# PatGenV2.net
KiCad netlist of a schematic drawn in EAGLE
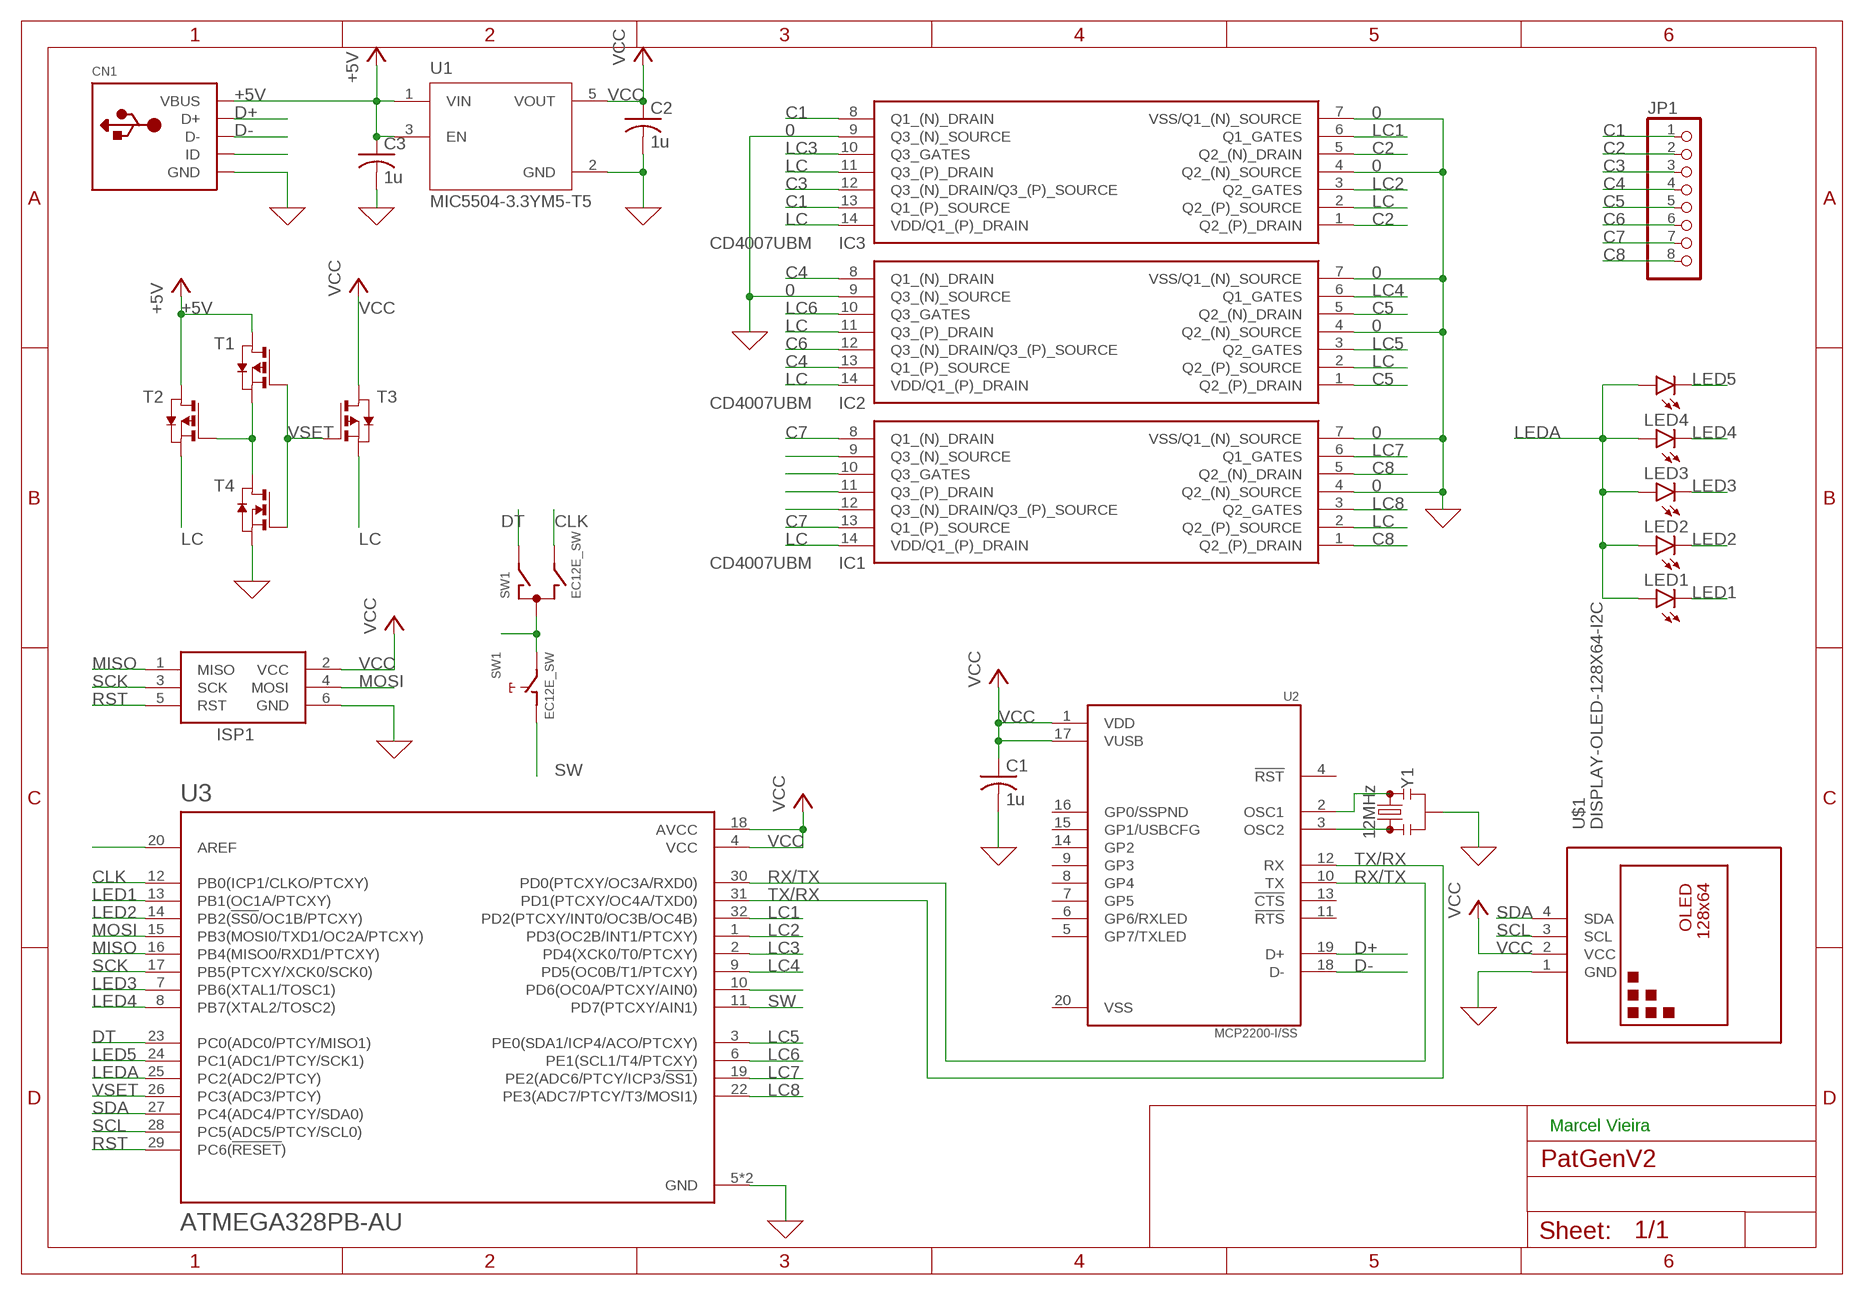
[diagram p0: schematic, sheet 1]

(export (version "E")
  (design (tool "Eeschema 10.0.6"))
  (components
    (comp (ref "C1")
      (value "1u")
      (footprint "eagle-import:C0805")
      (libsource (lib "eagle-import") (part "C-USC0805"))
    )
    (comp (ref "C2")
      (value "1u")
      (footprint "eagle-import:C0805")
      (libsource (lib "eagle-import") (part "C-USC0805"))
    )
    (comp (ref "C3")
      (value "1u")
      (footprint "eagle-import:C0805")
      (libsource (lib "eagle-import") (part "C-USC0805"))
    )
    (comp (ref "CN1")
      (value "USBMINIB")
      (footprint "eagle-import:USB-MINIB")
      (libsource (lib "eagle-import") (part "USBMINIB"))
    )
    (comp (ref "IC1")
      (value "CD4007UBM")
      (footprint "eagle-import:SOIC127P600X175-14N")
      (fields (field (name "MOUSER_PART_NUMBER") "595-CD4007UBM"))
      (libsource (lib "eagle-import") (part "CD4007UBM"))
    )
    (comp (ref "IC2")
      (value "CD4007UBM")
      (footprint "eagle-import:SOIC127P600X175-14N")
      (fields (field (name "MOUSER_PART_NUMBER") "595-CD4007UBM"))
      (libsource (lib "eagle-import") (part "CD4007UBM"))
    )
    (comp (ref "IC3")
      (value "CD4007UBM")
      (footprint "eagle-import:SOIC127P600X175-14N")
      (fields (field (name "MOUSER_PART_NUMBER") "595-CD4007UBM"))
      (libsource (lib "eagle-import") (part "CD4007UBM"))
    )
    (comp (ref "ISP1")
      (value "AVRISP-6")
      (footprint "eagle-import:AVRISP")
      (libsource (lib "eagle-import") (part "AVRISP-6"))
    )
    (comp (ref "JP1")
      (value "PINHD-1X8-3.5MM")
      (footprint "eagle-import:1X08-3.5MM")
      (libsource (lib "eagle-import") (part "PINHD-1X8-3.5MM"))
    )
    (comp (ref "LED1")
      (value "LEDCHIP-LED0805")
      (footprint "eagle-import:CHIP-LED0805")
      (libsource (lib "eagle-import") (part "LEDCHIP-LED0805"))
    )
    (comp (ref "LED2")
      (value "LEDCHIP-LED0805")
      (footprint "eagle-import:CHIP-LED0805")
      (libsource (lib "eagle-import") (part "LEDCHIP-LED0805"))
    )
    (comp (ref "LED3")
      (value "LEDCHIP-LED0805")
      (footprint "eagle-import:CHIP-LED0805")
      (libsource (lib "eagle-import") (part "LEDCHIP-LED0805"))
    )
    (comp (ref "LED4")
      (value "LEDCHIP-LED0805")
      (footprint "eagle-import:CHIP-LED0805")
      (libsource (lib "eagle-import") (part "LEDCHIP-LED0805"))
    )
    (comp (ref "LED5")
      (value "LEDCHIP-LED0805")
      (footprint "eagle-import:CHIP-LED0805")
      (libsource (lib "eagle-import") (part "LEDCHIP-LED0805"))
    )
    (comp (ref "SW1")
      (value "EC12E_SW")
      (footprint "eagle-import:ALPS_EC12E_SW")
      (fields (field (name "MPN") "EC12E2424407"))
      (libsource (lib "eagle-import") (part "EC12E_SW"))
    )
    (comp (ref "T1")
      (value "PMOSSOT23")
      (footprint "eagle-import:SOT-23")
      (libsource (lib "eagle-import") (part "PMOSSOT23"))
    )
    (comp (ref "T2")
      (value "PMOSSOT23")
      (footprint "eagle-import:SOT-23")
      (libsource (lib "eagle-import") (part "PMOSSOT23"))
    )
    (comp (ref "T3")
      (value "PMOSSOT23")
      (footprint "eagle-import:SOT-23")
      (libsource (lib "eagle-import") (part "PMOSSOT23"))
    )
    (comp (ref "T4")
      (value "NMOSSOT23")
      (footprint "eagle-import:SOT-23")
      (libsource (lib "eagle-import") (part "NMOSSOT23"))
    )
    (comp (ref "U$1")
      (value "DISPLAY-OLED-128X64-I2C")
      (footprint "eagle-import:DISPLAY-OLED-128X64-I2C")
      (libsource (lib "eagle-import") (part "DISPLAY-OLED-128X64-I2C"))
    )
    (comp (ref "U1")
      (value "MIC5504-3.3YM5-T5")
      (footprint "eagle-import:SOT95P280X145-5N")
      (fields (field (name "MF") "Microchip"))
      (libsource (lib "eagle-import") (part "MIC5504-3.3YM5-T5"))
    )
    (comp (ref "U2")
      (value "MCP2200-I/SS")
      (footprint "eagle-import:SOP65P780X200-20N")
      (fields (field (name "MF") "Microchip"))
      (libsource (lib "eagle-import") (part "MCP2200-I/SS"))
    )
    (comp (ref "U3")
      (value "ATMEGA328PB-AU")
      (footprint "eagle-import:QFP80P900X900X120-32N")
      (fields (field (name "MF") "Microchip Technology / Atmel"))
      (libsource (lib "eagle-import") (part "ATMEGA328PB-AU"))
    )
    (comp (ref "Y1")
      (value "12MHz")
      (footprint "eagle-import:RESONATOR-SMD-3.2X1.3")
      (libsource (lib "eagle-import") (part "RESONATOR-16MHZSMD_3.2X1.3"))
    )
  )
  (nets
    (net (code "1") (name "+5V") (class "Default")
      (node (ref "C3") (pin "1") (pinfunction "1_1") (pintype "passive"))
      (node (ref "CN1") (pin "VBUS") (pinfunction "VBUS_VBUS") (pintype "power_in"))
      (node (ref "T1") (pin "1") (pinfunction "D_1") (pintype "passive"))
      (node (ref "T2") (pin "1") (pinfunction "D_1") (pintype "passive"))
      (node (ref "U1") (pin "1") (pinfunction "VIN_1") (pintype "input"))
      (node (ref "U1") (pin "3") (pinfunction "EN_3") (pintype "input"))
    )
    (net (code "2") (name "/C1") (class "Default")
      (node (ref "IC3") (pin "13") (pinfunction "Q1_(P)_SOURCE_13") (pintype "bidirectional"))
      (node (ref "IC3") (pin "8") (pinfunction "Q1_(N)_DRAIN_8") (pintype "bidirectional"))
      (node (ref "JP1") (pin "1") (pinfunction "1_1") (pintype "passive"))
    )
    (net (code "3") (name "/C2") (class "Default")
      (node (ref "IC3") (pin "1") (pinfunction "Q2_(P)_DRAIN_1") (pintype "bidirectional"))
      (node (ref "IC3") (pin "5") (pinfunction "Q2_(N)_DRAIN_5") (pintype "bidirectional"))
      (node (ref "JP1") (pin "2") (pinfunction "2_2") (pintype "passive"))
    )
    (net (code "4") (name "/C3") (class "Default")
      (node (ref "IC3") (pin "12") (pinfunction "Q3_(N)_DRAIN/Q3_(P)_SOURCE_12") (pintype "bidirectional"))
      (node (ref "JP1") (pin "3") (pinfunction "3_3") (pintype "passive"))
    )
    (net (code "5") (name "/C4") (class "Default")
      (node (ref "IC2") (pin "13") (pinfunction "Q1_(P)_SOURCE_13") (pintype "bidirectional"))
      (node (ref "IC2") (pin "8") (pinfunction "Q1_(N)_DRAIN_8") (pintype "bidirectional"))
      (node (ref "JP1") (pin "4") (pinfunction "4_4") (pintype "passive"))
    )
    (net (code "6") (name "/C5") (class "Default")
      (node (ref "IC2") (pin "1") (pinfunction "Q2_(P)_DRAIN_1") (pintype "bidirectional"))
      (node (ref "IC2") (pin "5") (pinfunction "Q2_(N)_DRAIN_5") (pintype "bidirectional"))
      (node (ref "JP1") (pin "5") (pinfunction "5_5") (pintype "passive"))
    )
    (net (code "7") (name "/C6") (class "Default")
      (node (ref "IC2") (pin "12") (pinfunction "Q3_(N)_DRAIN/Q3_(P)_SOURCE_12") (pintype "bidirectional"))
      (node (ref "JP1") (pin "6") (pinfunction "6_6") (pintype "passive"))
    )
    (net (code "8") (name "/C7") (class "Default")
      (node (ref "IC1") (pin "13") (pinfunction "Q1_(P)_SOURCE_13") (pintype "bidirectional"))
      (node (ref "IC1") (pin "8") (pinfunction "Q1_(N)_DRAIN_8") (pintype "bidirectional"))
      (node (ref "JP1") (pin "7") (pinfunction "7_7") (pintype "passive"))
    )
    (net (code "9") (name "/C8") (class "Default")
      (node (ref "IC1") (pin "1") (pinfunction "Q2_(P)_DRAIN_1") (pintype "bidirectional"))
      (node (ref "IC1") (pin "5") (pinfunction "Q2_(N)_DRAIN_5") (pintype "bidirectional"))
      (node (ref "JP1") (pin "8") (pinfunction "8_8") (pintype "passive"))
    )
    (net (code "10") (name "/CLK") (class "Default")
      (node (ref "SW1") (pin "B") (pinfunction "B_B") (pintype "passive"))
      (node (ref "U3") (pin "12") (pinfunction "PB0(ICP1/CLKO/PTCXY)_12") (pintype "bidirectional"))
    )
    (net (code "11") (name "/D+") (class "Default")
      (node (ref "CN1") (pin "D+") (pinfunction "D+_D+") (pintype "bidirectional"))
      (node (ref "U2") (pin "19") (pinfunction "D+_19") (pintype "bidirectional"))
    )
    (net (code "12") (name "/D-") (class "Default")
      (node (ref "CN1") (pin "D-") (pinfunction "D-_D-") (pintype "bidirectional"))
      (node (ref "U2") (pin "18") (pinfunction "D-_18") (pintype "bidirectional"))
    )
    (net (code "13") (name "/DT") (class "Default")
      (node (ref "SW1") (pin "A") (pinfunction "A_A") (pintype "passive"))
      (node (ref "U3") (pin "23") (pinfunction "PC0(ADC0/PTCY/MISO1)_23") (pintype "bidirectional"))
    )
    (net (code "14") (name "/LC") (class "Default")
      (node (ref "IC1") (pin "14") (pinfunction "VDD/Q1_(P)_DRAIN_14") (pintype "bidirectional"))
      (node (ref "IC1") (pin "2") (pinfunction "Q2_(P)_SOURCE_2") (pintype "bidirectional"))
      (node (ref "IC2") (pin "11") (pinfunction "Q3_(P)_DRAIN_11") (pintype "bidirectional"))
      (node (ref "IC2") (pin "14") (pinfunction "VDD/Q1_(P)_DRAIN_14") (pintype "bidirectional"))
      (node (ref "IC2") (pin "2") (pinfunction "Q2_(P)_SOURCE_2") (pintype "bidirectional"))
      (node (ref "IC3") (pin "11") (pinfunction "Q3_(P)_DRAIN_11") (pintype "bidirectional"))
      (node (ref "IC3") (pin "14") (pinfunction "VDD/Q1_(P)_DRAIN_14") (pintype "bidirectional"))
      (node (ref "IC3") (pin "2") (pinfunction "Q2_(P)_SOURCE_2") (pintype "bidirectional"))
      (node (ref "T2") (pin "2") (pinfunction "S_2") (pintype "passive"))
      (node (ref "T3") (pin "2") (pinfunction "S_2") (pintype "passive"))
    )
    (net (code "15") (name "/LC1") (class "Default")
      (node (ref "IC3") (pin "6") (pinfunction "Q1_GATES_6") (pintype "bidirectional"))
      (node (ref "U3") (pin "32") (pinfunction "PD2(PTCXY/INT0/OC3B/OC4B)_32") (pintype "bidirectional"))
    )
    (net (code "16") (name "/LC2") (class "Default")
      (node (ref "IC3") (pin "3") (pinfunction "Q2_GATES_3") (pintype "bidirectional"))
      (node (ref "U3") (pin "1") (pinfunction "PD3(OC2B/INT1/PTCXY)_1") (pintype "bidirectional"))
    )
    (net (code "17") (name "/LC3") (class "Default")
      (node (ref "IC3") (pin "10") (pinfunction "Q3_GATES_10") (pintype "bidirectional"))
      (node (ref "U3") (pin "2") (pinfunction "PD4(XCK0/T0/PTCXY)_2") (pintype "bidirectional"))
    )
    (net (code "18") (name "/LC4") (class "Default")
      (node (ref "IC2") (pin "6") (pinfunction "Q1_GATES_6") (pintype "bidirectional"))
      (node (ref "U3") (pin "9") (pinfunction "PD5(OC0B/T1/PTCXY)_9") (pintype "bidirectional"))
    )
    (net (code "19") (name "/LC5") (class "Default")
      (node (ref "IC2") (pin "3") (pinfunction "Q2_GATES_3") (pintype "bidirectional"))
      (node (ref "U3") (pin "3") (pinfunction "PE0(SDA1/ICP4/ACO/PTCXY)_3") (pintype "bidirectional"))
    )
    (net (code "20") (name "/LC6") (class "Default")
      (node (ref "IC2") (pin "10") (pinfunction "Q3_GATES_10") (pintype "bidirectional"))
      (node (ref "U3") (pin "6") (pinfunction "PE1(SCL1/T4/PTCXY)_6") (pintype "bidirectional"))
    )
    (net (code "21") (name "/LC7") (class "Default")
      (node (ref "IC1") (pin "6") (pinfunction "Q1_GATES_6") (pintype "bidirectional"))
      (node (ref "U3") (pin "19") (pinfunction "PE2(ADC6/PTCY/ICP3/~{SS1})_19") (pintype "bidirectional"))
    )
    (net (code "22") (name "/LC8") (class "Default")
      (node (ref "IC1") (pin "3") (pinfunction "Q2_GATES_3") (pintype "bidirectional"))
      (node (ref "U3") (pin "22") (pinfunction "PE3(ADC7/PTCY/T3/MOSI1)_22") (pintype "bidirectional"))
    )
    (net (code "23") (name "/LED1") (class "Default")
      (node (ref "LED1") (pin "C") (pinfunction "C_C") (pintype "passive"))
      (node (ref "U3") (pin "13") (pinfunction "PB1(OC1A/PTCXY)_13") (pintype "bidirectional"))
    )
    (net (code "24") (name "/LED2") (class "Default")
      (node (ref "LED2") (pin "C") (pinfunction "C_C") (pintype "passive"))
      (node (ref "U3") (pin "14") (pinfunction "PB2(~{SS0}/OC1B/PTCXY)_14") (pintype "bidirectional"))
    )
    (net (code "25") (name "/LED3") (class "Default")
      (node (ref "LED3") (pin "C") (pinfunction "C_C") (pintype "passive"))
      (node (ref "U3") (pin "7") (pinfunction "PB6(XTAL1/TOSC1)_7") (pintype "bidirectional"))
    )
    (net (code "26") (name "/LED4") (class "Default")
      (node (ref "LED4") (pin "C") (pinfunction "C_C") (pintype "passive"))
      (node (ref "U3") (pin "8") (pinfunction "PB7(XTAL2/TOSC2)_8") (pintype "bidirectional"))
    )
    (net (code "27") (name "/LED5") (class "Default")
      (node (ref "LED5") (pin "C") (pinfunction "C_C") (pintype "passive"))
      (node (ref "U3") (pin "24") (pinfunction "PC1(ADC1/PTCY/SCK1)_24") (pintype "bidirectional"))
    )
    (net (code "28") (name "/LEDA") (class "Default")
      (node (ref "LED1") (pin "A") (pinfunction "A_A") (pintype "passive"))
      (node (ref "LED2") (pin "A") (pinfunction "A_A") (pintype "passive"))
      (node (ref "LED3") (pin "A") (pinfunction "A_A") (pintype "passive"))
      (node (ref "LED4") (pin "A") (pinfunction "A_A") (pintype "passive"))
      (node (ref "LED5") (pin "A") (pinfunction "A_A") (pintype "passive"))
      (node (ref "U3") (pin "25") (pinfunction "PC2(ADC2/PTCY)_25") (pintype "bidirectional"))
    )
    (net (code "29") (name "/MISO") (class "Default")
      (node (ref "ISP1") (pin "1") (pinfunction "MISO_1") (pintype "input"))
      (node (ref "U3") (pin "16") (pinfunction "PB4(MISO0/RXD1/PTCXY)_16") (pintype "bidirectional"))
    )
    (net (code "30") (name "/MOSI") (class "Default")
      (node (ref "ISP1") (pin "4") (pinfunction "MOSI_4") (pintype "output"))
      (node (ref "U3") (pin "15") (pinfunction "PB3(MOSI0/TXD1/OC2A/PTCXY)_15") (pintype "bidirectional"))
    )
    (net (code "31") (name "/RST") (class "Default")
      (node (ref "ISP1") (pin "5") (pinfunction "RST_5") (pintype "output"))
      (node (ref "U3") (pin "29") (pinfunction "PC6(~{RESET})_29") (pintype "bidirectional"))
    )
    (net (code "32") (name "/RX{slash}TX") (class "Default")
      (node (ref "U2") (pin "10") (pinfunction "TX_10") (pintype "output"))
      (node (ref "U3") (pin "30") (pinfunction "PD0(PTCXY/OC3A/RXD0)_30") (pintype "bidirectional"))
    )
    (net (code "33") (name "/SCK") (class "Default")
      (node (ref "ISP1") (pin "3") (pinfunction "SCK_3") (pintype "output"))
      (node (ref "U3") (pin "17") (pinfunction "PB5(PTCXY/XCK0/SCK0)_17") (pintype "bidirectional"))
    )
    (net (code "34") (name "/SCL") (class "Default")
      (node (ref "U$1") (pin "3") (pinfunction "SCL_3") (pintype "bidirectional"))
      (node (ref "U3") (pin "28") (pinfunction "PC5(ADC5/PTCY/SCL0)_28") (pintype "bidirectional"))
    )
    (net (code "35") (name "/SDA") (class "Default")
      (node (ref "U$1") (pin "4") (pinfunction "SDA_4") (pintype "bidirectional"))
      (node (ref "U3") (pin "27") (pinfunction "PC4(ADC4/PTCY/SDA0)_27") (pintype "bidirectional"))
    )
    (net (code "36") (name "/SW") (class "Default")
      (node (ref "SW1") (pin "D") (pinfunction "1_D") (pintype "passive"))
      (node (ref "U3") (pin "11") (pinfunction "PD7(PTCXY/AIN1)_11") (pintype "bidirectional"))
    )
    (net (code "37") (name "/TX{slash}RX") (class "Default")
      (node (ref "U2") (pin "12") (pinfunction "RX_12") (pintype "input"))
      (node (ref "U3") (pin "31") (pinfunction "PD1(PTCXY/OC4A/TXD0)_31") (pintype "bidirectional"))
    )
    (net (code "38") (name "/VSET") (class "Default")
      (node (ref "T1") (pin "3") (pinfunction "G_3") (pintype "passive"))
      (node (ref "T3") (pin "3") (pinfunction "G_3") (pintype "passive"))
      (node (ref "T4") (pin "3") (pinfunction "G_3") (pintype "passive"))
      (node (ref "U3") (pin "26") (pinfunction "PC3(ADC3/PTCY)_26") (pintype "bidirectional"))
    )
    (net (code "39") (name "/VSS") (class "Default")
      (node (ref "U2") (pin "20") (pinfunction "VSS_20") (pintype "power_in"))
    )
    (net (code "40") (name "GND") (class "Default")
      (node (ref "C1") (pin "2") (pinfunction "2_2") (pintype "passive"))
      (node (ref "C2") (pin "2") (pinfunction "2_2") (pintype "passive"))
      (node (ref "C3") (pin "2") (pinfunction "2_2") (pintype "passive"))
      (node (ref "CN1") (pin "GND") (pinfunction "GND_GND") (pintype "power_in"))
      (node (ref "IC1") (pin "4") (pinfunction "Q2_(N)_SOURCE_4") (pintype "bidirectional"))
      (node (ref "IC1") (pin "7") (pinfunction "VSS/Q1_(N)_SOURCE_7") (pintype "bidirectional"))
      (node (ref "IC2") (pin "4") (pinfunction "Q2_(N)_SOURCE_4") (pintype "bidirectional"))
      (node (ref "IC2") (pin "7") (pinfunction "VSS/Q1_(N)_SOURCE_7") (pintype "bidirectional"))
      (node (ref "IC2") (pin "9") (pinfunction "Q3_(N)_SOURCE_9") (pintype "bidirectional"))
      (node (ref "IC3") (pin "4") (pinfunction "Q2_(N)_SOURCE_4") (pintype "bidirectional"))
      (node (ref "IC3") (pin "7") (pinfunction "VSS/Q1_(N)_SOURCE_7") (pintype "bidirectional"))
      (node (ref "IC3") (pin "9") (pinfunction "Q3_(N)_SOURCE_9") (pintype "bidirectional"))
      (node (ref "ISP1") (pin "6") (pinfunction "GND_6") (pintype "power_in"))
      (node (ref "T4") (pin "2") (pinfunction "S_2") (pintype "passive"))
      (node (ref "U$1") (pin "1") (pinfunction "GND_1") (pintype "power_in"))
      (node (ref "U1") (pin "2") (pinfunction "GND_2") (pintype "power_in"))
      (node (ref "U3") (pin "21") (pinfunction "GND_21") (pintype "power_in"))
      (node (ref "U3") (pin "5") (pinfunction "GND_5") (pintype "power_in"))
      (node (ref "Y1") (pin "2") (pinfunction "2_2") (pintype "passive"))
    )
    (net (code "41") (name "Net-(SW1B-2)") (class "Default")
      (node (ref "SW1") (pin "C") (pinfunction "C_C") (pintype "passive"))
      (node (ref "SW1") (pin "E") (pinfunction "2_E") (pintype "passive"))
    )
    (net (code "42") (name "Net-(T1-S)") (class "Default")
      (node (ref "T1") (pin "2") (pinfunction "S_2") (pintype "passive"))
      (node (ref "T2") (pin "3") (pinfunction "G_3") (pintype "passive"))
      (node (ref "T4") (pin "1") (pinfunction "D_1") (pintype "passive"))
    )
    (net (code "43") (name "Net-(U2-OSC1)") (class "Default")
      (node (ref "U2") (pin "2") (pinfunction "OSC1_2") (pintype "input"))
      (node (ref "Y1") (pin "1") (pinfunction "1_1") (pintype "passive"))
    )
    (net (code "44") (name "Net-(U2-OSC2)") (class "Default")
      (node (ref "U2") (pin "3") (pinfunction "OSC2_3") (pintype "output"))
      (node (ref "Y1") (pin "3") (pinfunction "3_3") (pintype "passive"))
    )
    (net (code "45") (name "VCC") (class "Default")
      (node (ref "C1") (pin "1") (pinfunction "1_1") (pintype "passive"))
      (node (ref "C2") (pin "1") (pinfunction "1_1") (pintype "passive"))
      (node (ref "ISP1") (pin "2") (pinfunction "VCC_2") (pintype "power_in"))
      (node (ref "T3") (pin "1") (pinfunction "D_1") (pintype "passive"))
      (node (ref "U$1") (pin "2") (pinfunction "VCC_2") (pintype "power_in"))
      (node (ref "U1") (pin "5") (pinfunction "VOUT_5") (pintype "output"))
      (node (ref "U2") (pin "1") (pinfunction "VDD_1") (pintype "power_in"))
      (node (ref "U2") (pin "17") (pinfunction "VUSB_17") (pintype "power_in"))
      (node (ref "U3") (pin "18") (pinfunction "AVCC_18") (pintype "power_in"))
      (node (ref "U3") (pin "4") (pinfunction "VCC_4") (pintype "power_in"))
    )
    (net (code "46") (name "unconnected-(CN1-PadID)") (class "Default")
      (node (ref "CN1") (pin "ID") (pinfunction "ID_ID") (pintype "bidirectional"))
    )
    (net (code "47") (name "unconnected-(IC1-Q3_(N)_DRAIN{slash}Q3_(P)_SOURCE-Pad12)") (class "Default")
      (node (ref "IC1") (pin "12") (pinfunction "Q3_(N)_DRAIN/Q3_(P)_SOURCE_12") (pintype "bidirectional"))
    )
    (net (code "48") (name "unconnected-(IC1-Q3_(N)_SOURCE-Pad9)") (class "Default")
      (node (ref "IC1") (pin "9") (pinfunction "Q3_(N)_SOURCE_9") (pintype "bidirectional"))
    )
    (net (code "49") (name "unconnected-(IC1-Q3_(P)_DRAIN-Pad11)") (class "Default")
      (node (ref "IC1") (pin "11") (pinfunction "Q3_(P)_DRAIN_11") (pintype "bidirectional"))
    )
    (net (code "50") (name "unconnected-(IC1-Q3_GATES-Pad10)") (class "Default")
      (node (ref "IC1") (pin "10") (pinfunction "Q3_GATES_10") (pintype "bidirectional"))
    )
    (net (code "51") (name "unconnected-(U2-GP0{slash}SSPND-Pad16)") (class "Default")
      (node (ref "U2") (pin "16") (pinfunction "GP0/SSPND_16") (pintype "bidirectional"))
    )
    (net (code "52") (name "unconnected-(U2-GP1{slash}USBCFG-Pad15)") (class "Default")
      (node (ref "U2") (pin "15") (pinfunction "GP1/USBCFG_15") (pintype "bidirectional"))
    )
    (net (code "53") (name "unconnected-(U2-GP2-Pad14)") (class "Default")
      (node (ref "U2") (pin "14") (pinfunction "GP2_14") (pintype "bidirectional"))
    )
    (net (code "54") (name "unconnected-(U2-GP3-Pad9)") (class "Default")
      (node (ref "U2") (pin "9") (pinfunction "GP3_9") (pintype "bidirectional"))
    )
    (net (code "55") (name "unconnected-(U2-GP4-Pad8)") (class "Default")
      (node (ref "U2") (pin "8") (pinfunction "GP4_8") (pintype "bidirectional"))
    )
    (net (code "56") (name "unconnected-(U2-GP5-Pad7)") (class "Default")
      (node (ref "U2") (pin "7") (pinfunction "GP5_7") (pintype "bidirectional"))
    )
    (net (code "57") (name "unconnected-(U2-GP6{slash}RXLED-Pad6)") (class "Default")
      (node (ref "U2") (pin "6") (pinfunction "GP6/RXLED_6") (pintype "bidirectional"))
    )
    (net (code "58") (name "unconnected-(U2-GP7{slash}TXLED-Pad5)") (class "Default")
      (node (ref "U2") (pin "5") (pinfunction "GP7/TXLED_5") (pintype "bidirectional"))
    )
    (net (code "59") (name "unconnected-(U2-~{CTS}-Pad13)") (class "Default")
      (node (ref "U2") (pin "13") (pinfunction "~{CTS}_13") (pintype "input"))
    )
    (net (code "60") (name "unconnected-(U2-~{RST}-Pad4)") (class "Default")
      (node (ref "U2") (pin "4") (pinfunction "~{RST}_4") (pintype "input"))
    )
    (net (code "61") (name "unconnected-(U2-~{RTS}-Pad11)") (class "Default")
      (node (ref "U2") (pin "11") (pinfunction "~{RTS}_11") (pintype "output"))
    )
    (net (code "62") (name "unconnected-(U3-AREF-Pad20)") (class "Default")
      (node (ref "U3") (pin "20") (pinfunction "AREF_20") (pintype "input"))
    )
    (net (code "63") (name "unconnected-(U3-PD6(OC0A{slash}PTCXY{slash}AIN0)-Pad10)") (class "Default")
      (node (ref "U3") (pin "10") (pinfunction "PD6(OC0A/PTCXY/AIN0)_10") (pintype "bidirectional"))
    )
  )
)
